# main.net
KiCad netlist of a schematic drawn in Altium Designer
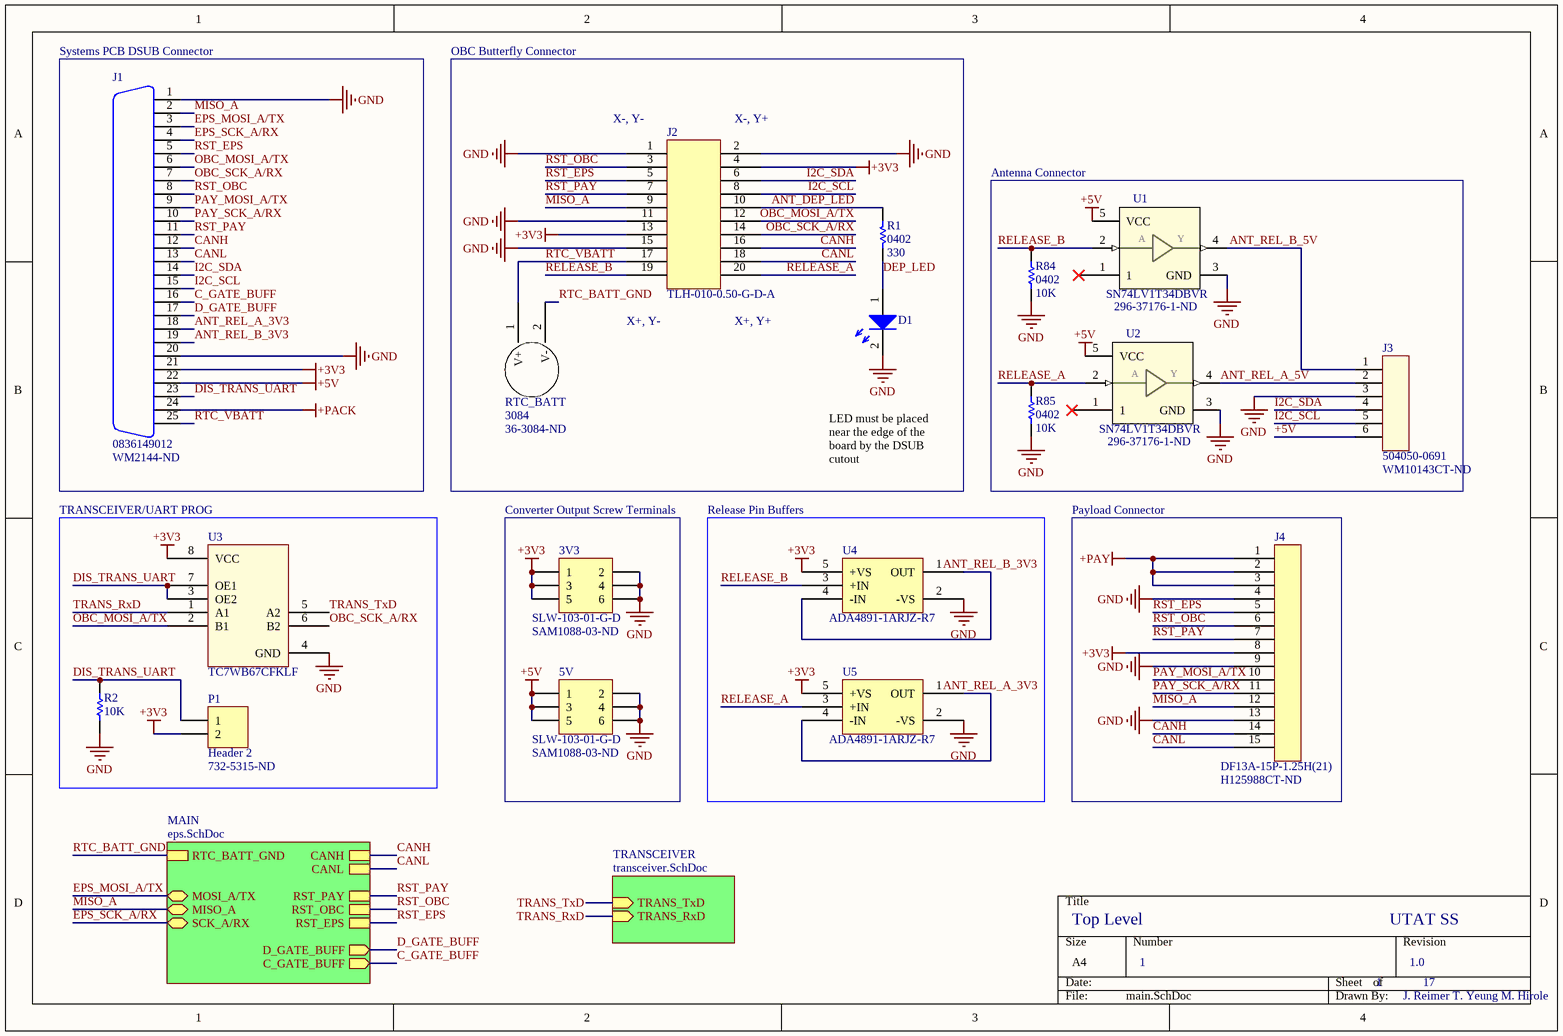
[diagram p0: main.SchDoc]

(export (version "E")
  (design (tool "Eeschema 10.0.6"))
  (components
    (comp (ref "3V3")
      (value "SLW-103-01-G-D")
      (footprint "SLW-103-01-X-D")
      (description "6 pos 100mil pitch low profile header")
      (fields (field (name "SUPPLIER PART NUMBER 1") "SAM1088-03-ND"))
      (libsource (lib "heron-general") (part "SLW-103-01-G-D"))
    )
    (comp (ref "5V")
      (value "SLW-103-01-G-D")
      (footprint "SLW-103-01-X-D")
      (description "6 pos 100mil pitch low profile header")
      (fields (field (name "SUPPLIER PART NUMBER 1") "SAM1088-03-ND"))
      (libsource (lib "heron-general") (part "SLW-103-01-G-D"))
    )
    (comp (ref "D1")
      (value "~")
      (footprint "LED0603")
      (description "Just a generic LED")
      (libsource (lib "heron-general") (part "LED"))
    )
    (comp (ref "J1")
      (value "0836149012")
      (footprint "0836149012")
      (description "Mini-DSUB 25-pos Connector")
      (fields (field (name "SUPPLIER PART NUMBER 1") "WM2144-ND"))
      (libsource (lib "heron-general") (part "0836149012"))
    )
    (comp (ref "J2")
      (value "TLH-010-0.50-G-D-A")
      (footprint "TLH-010-0.50-G-D-A")
      (description "0.50 mm Razor Beam LP Ultra Low Profile Terminal Strip, alignment pin option")
      (libsource (lib "heron-general") (part "TLH-010-0.50-G-D-A"))
    )
    (comp (ref "J3")
      (value "504050-0691")
      (footprint "MOLEX_504050-0691:MOLEX_504050-0691")
      (description "Wire-To-Board Connector, Pico-Lock 504050 Series, Surface Mount, Header, 6, 1.5 mm")
      (fields (field (name "SUPPLIER PART NUMBER 1") "WM10143CT-ND"))
      (libsource (lib "504050-0691") (part "504050-0691"))
    )
    (comp (ref "J4")
      (value "DF13A-15P-1.25H(21)")
      (footprint "DF13A-15P-1.25H(21)")
      (description "15 pos DF13 right angle surface mount connector")
      (fields (field (name "SUPPLIER PART NUMBER 1") "H125988CT-ND"))
      (libsource (lib "heron-general") (part "DF13A-15P-1.25H(21)"))
    )
    (comp (ref "P1")
      (value "Header 2")
      (footprint "HDR1X2")
      (description "Header, 2-Pin")
      (fields
        (field (name "SUPPLIER PART NUMBER 1") "732-5315-ND")
        (field (name "PUBLISHER") "Altium Limited")
      )
      (libsource (lib "Miscellaneous Connectors") (part "Header 2"))
    )
    (comp (ref "R1")
      (value "0402")
      (footprint "RES0402R")
      (description "0402 resistor")
      (fields (field (name "ALTIUM_VALUE") "330"))
      (libsource (lib "heron-general") (part "RES0402"))
    )
    (comp (ref "R2")
      (value "10K")
      (footprint "RES0402R")
      (description "0402 resistor")
      (fields (field (name "Comment") "0402"))
      (libsource (lib "heron-general") (part "RES0402"))
    )
    (comp (ref "R84")
      (value "0402")
      (footprint "RES0402R")
      (description "0402 resistor")
      (fields (field (name "ALTIUM_VALUE") "10K"))
      (libsource (lib "heron-general") (part "RES0402"))
    )
    (comp (ref "R85")
      (value "0402")
      (footprint "RES0402R")
      (description "0402 resistor")
      (fields (field (name "ALTIUM_VALUE") "10K"))
      (libsource (lib "heron-general") (part "RES0402"))
    )
    (comp (ref "RTC_BATT")
      (value "3084")
      (footprint "3084")
      (description "CR2330 Battery Holder")
      (fields
        (field (name "MANUFACTURER") "Keystone Electronics")
        (field (name "SUPPLIER PART NUMBER 1") "36-3084-ND")
      )
      (libsource (lib "heron-general") (part "3084"))
    )
    (comp (ref "U1")
      (value "SN74LV1T34DBVR")
      (footprint "SOT95P280X145-5N")
      (description "Single Power Supply BUFFER Logic Level Shifter _no enable_ 5-SOT-23 -40 to 125")
      (fields
        (field (name "MF") "Texas Instruments")
        (field (name "DIGI-KEY_PART_NUMBER") "296-37176-1-ND")
        (field (name "SUPPLIER PART NUMBER 1") "296-37176-1-ND")
      )
      (libsource (lib "heron-general") (part "SN74LV1T34DBVR"))
    )
    (comp (ref "U2")
      (value "SN74LV1T34DBVR")
      (footprint "SOT95P280X145-5N")
      (description "Single Power Supply BUFFER Logic Level Shifter _no enable_ 5-SOT-23 -40 to 125")
      (fields
        (field (name "MF") "Texas Instruments")
        (field (name "DIGI-KEY_PART_NUMBER") "296-37176-1-ND")
        (field (name "SUPPLIER PART NUMBER 1") "296-37176-1-ND")
      )
      (libsource (lib "heron-general") (part "SN74LV1T34DBVR"))
    )
    (comp (ref "U3")
      (value "TC7WB67CFKLF")
      (footprint "US8")
      (description "Active high bus switch")
      (fields
        (field (name "MANUFACTURER") "Toshiba")
        (field (name "MANUFACTURER PART NUMBER") "TC7WB67CFK,LF(CT")
      )
      (libsource (lib "heron-general") (part "TC7WB66CFKLF"))
    )
    (comp (ref "U4")
      (value "ADA4891-1ARJZ-R7")
      (footprint "SOT-23-5")
      (description "Rail-to-rail amplifier 125mA max")
      (fields (field (name "COPYRIGHT") "Copyright (C) 2018 Accelerated Designs. All rights reserved"))
      (libsource (lib "heron-general") (part "ADA4891-1ARJZ-R7"))
    )
    (comp (ref "U5")
      (value "ADA4891-1ARJZ-R7")
      (footprint "SOT-23-5")
      (description "Rail-to-rail amplifier 125mA max")
      (fields (field (name "COPYRIGHT") "Copyright (C) 2018 Accelerated Designs. All rights reserved"))
      (libsource (lib "heron-general") (part "ADA4891-1ARJZ-R7"))
    )
  )
  (nets
    (net (code "1") (name "+3V3") (class "Default")
      (node (ref "3V3") (pin "1") (pinfunction "1_1") (pintype "passive"))
      (node (ref "3V3") (pin "3") (pinfunction "3_3") (pintype "passive"))
      (node (ref "3V3") (pin "5") (pinfunction "5_5") (pintype "passive"))
      (node (ref "J1") (pin "21") (pinfunction "21_21") (pintype "passive"))
      (node (ref "J2") (pin "13") (pintype "passive"))
      (node (ref "J2") (pin "4") (pintype "passive"))
      (node (ref "J4") (pin "8") (pintype "passive"))
      (node (ref "P1") (pin "2") (pinfunction "2_2") (pintype "passive"))
      (node (ref "U3") (pin "8") (pinfunction "VCC_8") (pintype "passive"))
      (node (ref "U4") (pin "5") (pinfunction "+VS_5") (pintype "passive"))
      (node (ref "U5") (pin "5") (pinfunction "+VS_5") (pintype "passive"))
    )
    (net (code "2") (name "+5V") (class "Default")
      (node (ref "5V") (pin "1") (pinfunction "1_1") (pintype "passive"))
      (node (ref "5V") (pin "3") (pinfunction "3_3") (pintype "passive"))
      (node (ref "5V") (pin "5") (pinfunction "5_5") (pintype "passive"))
      (node (ref "J1") (pin "22") (pinfunction "22_22") (pintype "passive"))
      (node (ref "J3") (pin "6") (pinfunction "6_6") (pintype "passive"))
      (node (ref "U1") (pin "5") (pinfunction "VCC_5") (pintype "power_in"))
      (node (ref "U2") (pin "5") (pinfunction "VCC_5") (pintype "power_in"))
    )
    (net (code "3") (name "+PACK") (class "Default")
      (node (ref "J1") (pin "24") (pinfunction "24_24") (pintype "passive"))
    )
    (net (code "4") (name "+PAY") (class "Default")
      (node (ref "J4") (pin "1") (pintype "passive"))
      (node (ref "J4") (pin "2") (pintype "passive"))
      (node (ref "J4") (pin "3") (pintype "passive"))
    )
    (net (code "5") (name "/ANT_DEP_LED") (class "Default")
      (node (ref "J2") (pin "10") (pintype "passive"))
      (node (ref "R1") (pin "2") (pinfunction "2_2") (pintype "passive"))
    )
    (net (code "6") (name "/ANT_REL_A_3V3") (class "Default")
      (node (ref "J1") (pin "18") (pinfunction "18_18") (pintype "passive"))
      (node (ref "U5") (pin "1") (pinfunction "OUT_1") (pintype "passive"))
      (node (ref "U5") (pin "4") (pinfunction "-IN_4") (pintype "passive"))
    )
    (net (code "7") (name "/ANT_REL_A_5V") (class "Default")
      (node (ref "J3") (pin "2") (pinfunction "2_2") (pintype "passive"))
      (node (ref "U2") (pin "4") (pinfunction "Y_4") (pintype "output"))
    )
    (net (code "8") (name "/ANT_REL_B_3V3") (class "Default")
      (node (ref "J1") (pin "19") (pinfunction "19_19") (pintype "passive"))
      (node (ref "U4") (pin "1") (pinfunction "OUT_1") (pintype "passive"))
      (node (ref "U4") (pin "4") (pinfunction "-IN_4") (pintype "passive"))
    )
    (net (code "9") (name "/ANT_REL_B_5V") (class "Default")
      (node (ref "J3") (pin "1") (pinfunction "1_1") (pintype "passive"))
      (node (ref "U1") (pin "4") (pinfunction "Y_4") (pintype "output"))
    )
    (net (code "10") (name "/CANH") (class "Default")
      (node (ref "J1") (pin "12") (pinfunction "12_12") (pintype "passive"))
      (node (ref "J2") (pin "16") (pintype "passive"))
      (node (ref "J4") (pin "14") (pintype "passive"))
    )
    (net (code "11") (name "/CANL") (class "Default")
      (node (ref "J1") (pin "13") (pinfunction "13_13") (pintype "passive"))
      (node (ref "J2") (pin "18") (pintype "passive"))
      (node (ref "J4") (pin "15") (pintype "passive"))
    )
    (net (code "12") (name "/C_GATE_BUFF") (class "Default")
      (node (ref "J1") (pin "16") (pinfunction "16_16") (pintype "passive"))
    )
    (net (code "13") (name "/DEP_LED") (class "Default")
      (node (ref "D1") (pin "1") (pinfunction "1_1") (pintype "passive"))
      (node (ref "R1") (pin "1") (pinfunction "1_1") (pintype "passive"))
    )
    (net (code "14") (name "/DIS_TRANS_UART") (class "Default")
      (node (ref "J1") (pin "23") (pinfunction "23_23") (pintype "passive"))
      (node (ref "P1") (pin "1") (pinfunction "1_1") (pintype "passive"))
      (node (ref "R2") (pin "1") (pinfunction "1_1") (pintype "passive"))
      (node (ref "U3") (pin "3") (pinfunction "OE2_3") (pintype "passive"))
      (node (ref "U3") (pin "7") (pinfunction "OE1_7") (pintype "passive"))
    )
    (net (code "15") (name "/D_GATE_BUFF") (class "Default")
      (node (ref "J1") (pin "17") (pinfunction "17_17") (pintype "passive"))
    )
    (net (code "16") (name "/EPS_MOSI_A{slash}TX") (class "Default")
      (node (ref "J1") (pin "3") (pinfunction "3_3") (pintype "passive"))
    )
    (net (code "17") (name "/EPS_SCK_A{slash}RX") (class "Default")
      (node (ref "J1") (pin "4") (pinfunction "4_4") (pintype "passive"))
    )
    (net (code "18") (name "/I2C_SCL") (class "Default")
      (node (ref "J1") (pin "15") (pinfunction "15_15") (pintype "passive"))
      (node (ref "J2") (pin "8") (pintype "passive"))
      (node (ref "J3") (pin "5") (pinfunction "5_5") (pintype "passive"))
    )
    (net (code "19") (name "/I2C_SDA") (class "Default")
      (node (ref "J1") (pin "14") (pinfunction "14_14") (pintype "passive"))
      (node (ref "J2") (pin "6") (pintype "passive"))
      (node (ref "J3") (pin "4") (pinfunction "4_4") (pintype "passive"))
    )
    (net (code "20") (name "/MISO_A") (class "Default")
      (node (ref "J1") (pin "2") (pinfunction "2_2") (pintype "passive"))
      (node (ref "J2") (pin "9") (pintype "passive"))
      (node (ref "J4") (pin "12") (pintype "passive"))
    )
    (net (code "21") (name "/OBC_MOSI_A{slash}TX") (class "Default")
      (node (ref "J1") (pin "6") (pinfunction "6_6") (pintype "passive"))
      (node (ref "J2") (pin "12") (pintype "passive"))
      (node (ref "U3") (pin "2") (pinfunction "B1_2") (pintype "passive"))
    )
    (net (code "22") (name "/OBC_SCK_A{slash}RX") (class "Default")
      (node (ref "J1") (pin "7") (pinfunction "7_7") (pintype "passive"))
      (node (ref "J2") (pin "14") (pintype "passive"))
      (node (ref "U3") (pin "6") (pinfunction "B2_6") (pintype "passive"))
    )
    (net (code "23") (name "/PAY_MOSI_A{slash}TX") (class "Default")
      (node (ref "J1") (pin "9") (pinfunction "9_9") (pintype "passive"))
      (node (ref "J4") (pin "10") (pintype "passive"))
    )
    (net (code "24") (name "/PAY_SCK_A{slash}RX") (class "Default")
      (node (ref "J1") (pin "10") (pinfunction "10_10") (pintype "passive"))
      (node (ref "J4") (pin "11") (pintype "passive"))
    )
    (net (code "25") (name "/RELEASE_A") (class "Default")
      (node (ref "J2") (pin "20") (pintype "passive"))
      (node (ref "R85") (pin "2") (pinfunction "2_2") (pintype "passive"))
      (node (ref "U2") (pin "2") (pinfunction "A_2") (pintype "input"))
      (node (ref "U5") (pin "3") (pinfunction "+IN_3") (pintype "passive"))
    )
    (net (code "26") (name "/RELEASE_B") (class "Default")
      (node (ref "J2") (pin "19") (pintype "passive"))
      (node (ref "R84") (pin "2") (pinfunction "2_2") (pintype "passive"))
      (node (ref "U1") (pin "2") (pinfunction "A_2") (pintype "input"))
      (node (ref "U4") (pin "3") (pinfunction "+IN_3") (pintype "passive"))
    )
    (net (code "27") (name "/RST_EPS") (class "Default")
      (node (ref "J1") (pin "5") (pinfunction "5_5") (pintype "passive"))
      (node (ref "J2") (pin "5") (pintype "passive"))
      (node (ref "J4") (pin "5") (pintype "passive"))
    )
    (net (code "28") (name "/RST_OBC") (class "Default")
      (node (ref "J1") (pin "8") (pinfunction "8_8") (pintype "passive"))
      (node (ref "J2") (pin "3") (pintype "passive"))
      (node (ref "J4") (pin "6") (pintype "passive"))
    )
    (net (code "29") (name "/RST_PAY") (class "Default")
      (node (ref "J1") (pin "11") (pinfunction "11_11") (pintype "passive"))
      (node (ref "J2") (pin "7") (pintype "passive"))
      (node (ref "J4") (pin "7") (pintype "passive"))
    )
    (net (code "30") (name "/RTC_BATT_GND") (class "Default")
      (node (ref "RTC_BATT") (pin "2") (pinfunction "V-_2") (pintype "passive"))
    )
    (net (code "31") (name "/RTC_VBATT") (class "Default")
      (node (ref "J1") (pin "25") (pinfunction "25_25") (pintype "passive"))
      (node (ref "J2") (pin "17") (pintype "passive"))
      (node (ref "RTC_BATT") (pin "1") (pinfunction "V+_1") (pintype "passive"))
    )
    (net (code "32") (name "/TRANS_RxD") (class "Default")
      (node (ref "U3") (pin "1") (pinfunction "A1_1") (pintype "passive"))
    )
    (net (code "33") (name "/TRANS_TxD") (class "Default")
      (node (ref "U3") (pin "5") (pinfunction "A2_5") (pintype "passive"))
    )
    (net (code "34") (name "GND") (class "Default")
      (node (ref "3V3") (pin "2") (pinfunction "2_2") (pintype "passive"))
      (node (ref "3V3") (pin "4") (pinfunction "4_4") (pintype "passive"))
      (node (ref "3V3") (pin "6") (pinfunction "6_6") (pintype "passive"))
      (node (ref "5V") (pin "2") (pinfunction "2_2") (pintype "passive"))
      (node (ref "5V") (pin "4") (pinfunction "4_4") (pintype "passive"))
      (node (ref "5V") (pin "6") (pinfunction "6_6") (pintype "passive"))
      (node (ref "D1") (pin "2") (pinfunction "2_2") (pintype "passive"))
      (node (ref "J1") (pin "1") (pinfunction "1_1") (pintype "passive"))
      (node (ref "J1") (pin "20") (pinfunction "20_20") (pintype "passive"))
      (node (ref "J2") (pin "1") (pintype "passive"))
      (node (ref "J2") (pin "11") (pintype "passive"))
      (node (ref "J2") (pin "15") (pintype "passive"))
      (node (ref "J2") (pin "2") (pintype "passive"))
      (node (ref "J3") (pin "3") (pinfunction "3_3") (pintype "passive"))
      (node (ref "J4") (pin "13") (pintype "passive"))
      (node (ref "J4") (pin "4") (pintype "passive"))
      (node (ref "J4") (pin "9") (pintype "passive"))
      (node (ref "R2") (pin "2") (pinfunction "2_2") (pintype "passive"))
      (node (ref "R84") (pin "1") (pinfunction "1_1") (pintype "passive"))
      (node (ref "R85") (pin "1") (pinfunction "1_1") (pintype "passive"))
      (node (ref "U1") (pin "3") (pinfunction "GND_3") (pintype "power_in"))
      (node (ref "U2") (pin "3") (pinfunction "GND_3") (pintype "power_in"))
      (node (ref "U3") (pin "4") (pinfunction "GND_4") (pintype "passive"))
      (node (ref "U4") (pin "2") (pinfunction "-VS_2") (pintype "passive"))
      (node (ref "U5") (pin "2") (pinfunction "-VS_2") (pintype "passive"))
    )
    (net (code "35") (name "unconnected-(U1-Pad1)") (class "Default")
      (node (ref "U1") (pin "1") (pinfunction "1_1") (pintype "passive+no_connect"))
    )
    (net (code "36") (name "unconnected-(U2-Pad1)") (class "Default")
      (node (ref "U2") (pin "1") (pinfunction "1_1") (pintype "passive+no_connect"))
    )
  )
)
